# Huu_Binh_IOT.net
KiCad netlist of a schematic drawn in Altium Designer
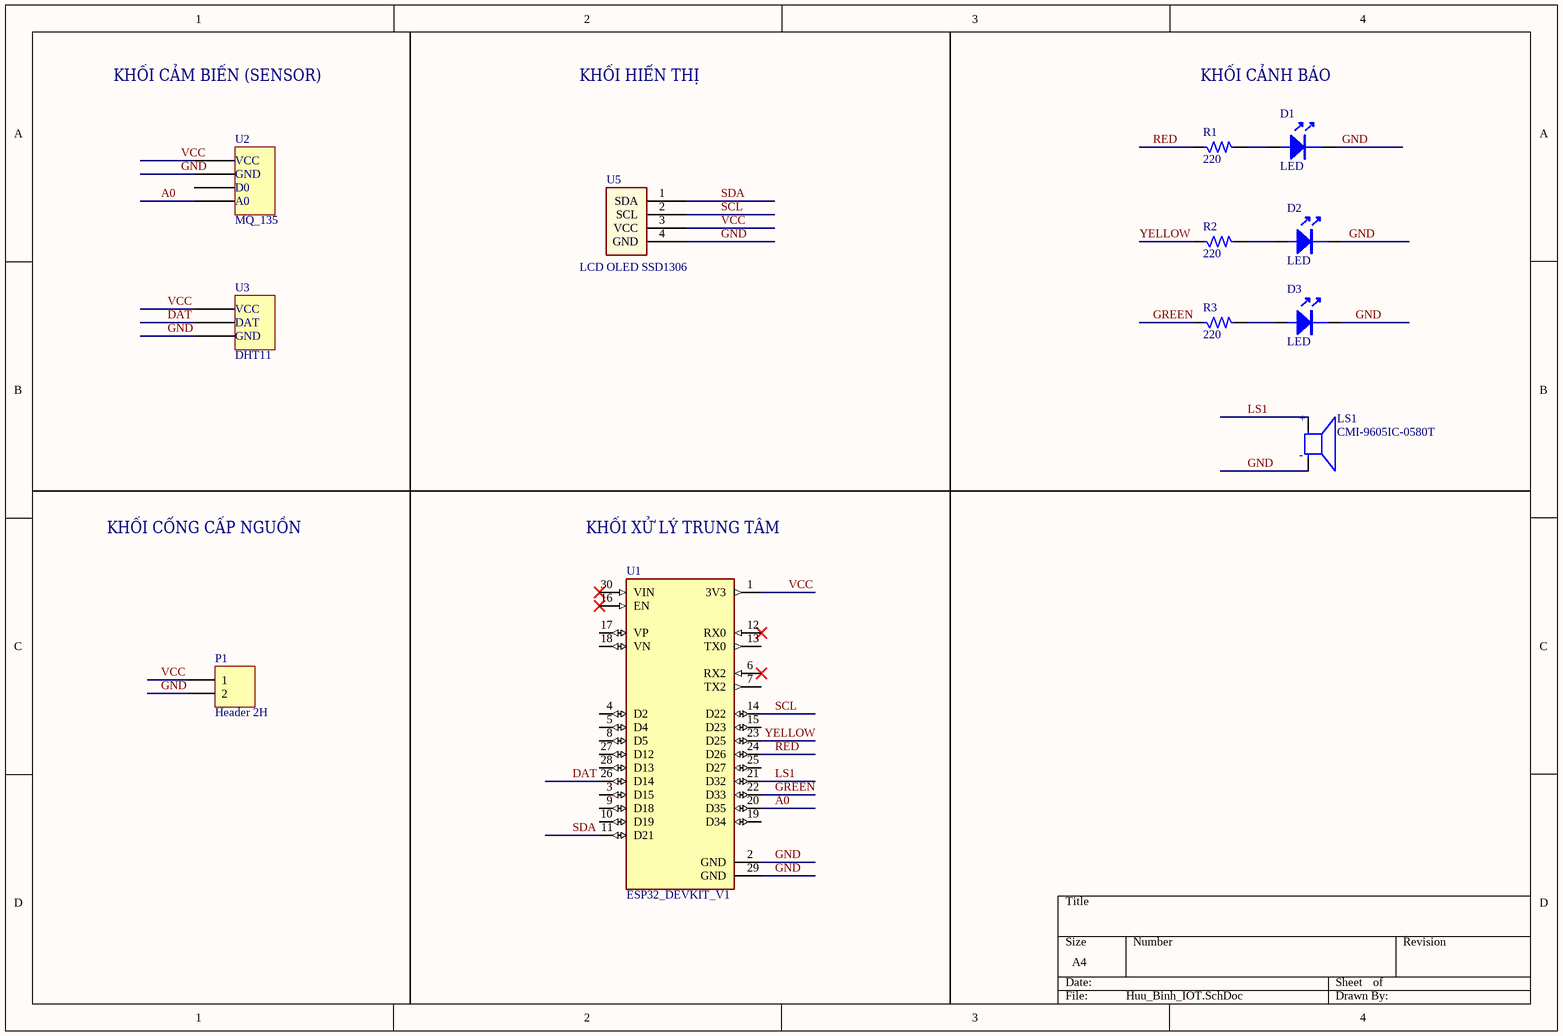
[diagram p0: Huu_Binh_IOT.SchDoc]

(export (version "E")
  (design (tool "Eeschema 10.0.6"))
  (components
    (comp (ref "D1") (value "LED") (footprint "CAP10UF") (libsource (lib "Devzone_SCHLib") (part "LED")))
    (comp (ref "D2") (value "LED") (footprint "CAP10UF") (libsource (lib "Devzone_SCHLib") (part "LED")))
    (comp (ref "D3") (value "LED") (footprint "CAP10UF") (libsource (lib "Devzone_SCHLib") (part "LED")))
    (comp (ref "LS1")
      (value "CMI-9605IC-0580T")
      (footprint "CUI_CMI-9605IC-0580T")
      (description "9.6 mm, 5 Vdc, 80 dB, Through Hole, Driving Circuit, Magnetic Audio Indicator Buzzer")
      (fields (field (name "MF") "Same Sky"))
      (libsource (lib "CMI-9605IC-0580T") (part "CMI-9605IC-0580T"))
    )
    (comp (ref "P1")
      (value "Header 2H")
      (footprint "HDR1X2H")
      (description "Header, 2-Pin, Right Angle")
      (fields (field (name "PUBLISHER") "Altium Limited"))
      (libsource (lib "Cty1") (part "Header 2H"))
    )
    (comp (ref "R1")
      (value "220")
      (footprint "R1/6W")
      (description "Resistor 1/4W")
      (libsource (lib "Devzone_SCHLib") (part "Res"))
    )
    (comp (ref "R2")
      (value "220")
      (footprint "R1/6W")
      (description "Resistor 1/4W")
      (libsource (lib "Devzone_SCHLib") (part "Res"))
    )
    (comp (ref "R3")
      (value "220")
      (footprint "R1/6W")
      (description "Resistor 1/4W")
      (libsource (lib "Devzone_SCHLib") (part "Res"))
    )
    (comp (ref "U1")
      (value "ESP32_DEVKIT_V1")
      (footprint "ESP32_DEVKIT_V1")
      (libsource (lib "ESP32_DEVKIT_V1") (part "ESP32_DEVKIT_V1"))
    )
    (comp (ref "U2") (value "MQ_135") (footprint "MQ_135") (libsource (lib "MQ_135_SCH") (part "MQ_135")))
    (comp (ref "U3") (value "DHT11") (footprint "DHT11") (libsource (lib "DHT11_SCH") (part "DHT11")))
    (comp (ref "U5")
      (value "LCD OLED SSD1306")
      (footprint "LCD SH1106")
      (libsource (lib "HoangLong_Library") (part "LCD SH1106"))
    )
  )
  (nets
    (net (code "1") (name "/A0") (class "Default")
      (node (ref "U1") (pin "20") (pinfunction "D35_20") (pintype "bidirectional"))
      (node (ref "U2") (pin "4") (pinfunction "3_4") (pintype "passive"))
    )
    (net (code "2") (name "/DAT") (class "Default")
      (node (ref "U1") (pin "26") (pinfunction "D14_26") (pintype "bidirectional"))
      (node (ref "U3") (pin "2") (pinfunction "2_2") (pintype "passive"))
    )
    (net (code "3") (name "/GND") (class "Default")
      (node (ref "D1") (pin "2") (pinfunction "2_2") (pintype "passive"))
      (node (ref "D2") (pin "2") (pinfunction "2_2") (pintype "passive"))
      (node (ref "D3") (pin "2") (pinfunction "2_2") (pintype "passive"))
      (node (ref "LS1") (pin "N") (pinfunction "N_N") (pintype "passive"))
      (node (ref "P1") (pin "2") (pinfunction "2_2") (pintype "passive"))
      (node (ref "U1") (pin "2") (pinfunction "GND_2") (pintype "power_in"))
      (node (ref "U1") (pin "29") (pinfunction "GND_29") (pintype "power_in"))
      (node (ref "U2") (pin "2") (pinfunction "2_2") (pintype "passive"))
      (node (ref "U3") (pin "3") (pinfunction "3_3") (pintype "passive"))
      (node (ref "U5") (pin "4") (pinfunction "GND_4") (pintype "passive"))
    )
    (net (code "4") (name "/GREEN") (class "Default")
      (node (ref "R3") (pin "1") (pinfunction "1_1") (pintype "passive"))
      (node (ref "U1") (pin "22") (pinfunction "D33_22") (pintype "bidirectional"))
    )
    (net (code "5") (name "/LS1") (class "Default")
      (node (ref "LS1") (pin "P") (pinfunction "P_P") (pintype "passive"))
      (node (ref "U1") (pin "21") (pinfunction "D32_21") (pintype "bidirectional"))
    )
    (net (code "6") (name "/RED") (class "Default")
      (node (ref "R1") (pin "1") (pinfunction "1_1") (pintype "passive"))
      (node (ref "U1") (pin "24") (pinfunction "D26_24") (pintype "bidirectional"))
    )
    (net (code "7") (name "/SCL") (class "Default")
      (node (ref "U1") (pin "14") (pinfunction "D22_14") (pintype "bidirectional"))
      (node (ref "U5") (pin "2") (pinfunction "SCL_2") (pintype "passive"))
    )
    (net (code "8") (name "/SDA") (class "Default")
      (node (ref "U1") (pin "11") (pinfunction "D21_11") (pintype "bidirectional"))
      (node (ref "U5") (pin "1") (pinfunction "SDA_1") (pintype "passive"))
    )
    (net (code "9") (name "/VCC") (class "Default")
      (node (ref "P1") (pin "1") (pinfunction "1_1") (pintype "passive"))
      (node (ref "U1") (pin "1") (pinfunction "3V3_1") (pintype "output"))
      (node (ref "U2") (pin "1") (pinfunction "1_1") (pintype "passive"))
      (node (ref "U3") (pin "1") (pinfunction "1_1") (pintype "passive"))
      (node (ref "U5") (pin "3") (pinfunction "VCC_3") (pintype "passive"))
    )
    (net (code "10") (name "/YELLOW") (class "Default")
      (node (ref "R2") (pin "1") (pinfunction "1_1") (pintype "passive"))
      (node (ref "U1") (pin "23") (pinfunction "D25_23") (pintype "bidirectional"))
    )
    (net (code "11") (name "Net-(D1-Pad1)") (class "Default")
      (node (ref "D1") (pin "1") (pinfunction "1_1") (pintype "passive"))
      (node (ref "R1") (pin "2") (pinfunction "2_2") (pintype "passive"))
    )
    (net (code "12") (name "Net-(D2-Pad1)") (class "Default")
      (node (ref "D2") (pin "1") (pinfunction "1_1") (pintype "passive"))
      (node (ref "R2") (pin "2") (pinfunction "2_2") (pintype "passive"))
    )
    (net (code "13") (name "Net-(D3-Pad1)") (class "Default")
      (node (ref "D3") (pin "1") (pinfunction "1_1") (pintype "passive"))
      (node (ref "R3") (pin "2") (pinfunction "2_2") (pintype "passive"))
    )
    (net (code "14") (name "unconnected-(U1-D2-Pad4)") (class "Default")
      (node (ref "U1") (pin "4") (pinfunction "D2_4") (pintype "bidirectional"))
    )
    (net (code "15") (name "unconnected-(U1-D4-Pad5)") (class "Default")
      (node (ref "U1") (pin "5") (pinfunction "D4_5") (pintype "bidirectional"))
    )
    (net (code "16") (name "unconnected-(U1-D5-Pad8)") (class "Default")
      (node (ref "U1") (pin "8") (pinfunction "D5_8") (pintype "bidirectional"))
    )
    (net (code "17") (name "unconnected-(U1-D12-Pad27)") (class "Default")
      (node (ref "U1") (pin "27") (pinfunction "D12_27") (pintype "bidirectional"))
    )
    (net (code "18") (name "unconnected-(U1-D13-Pad28)") (class "Default")
      (node (ref "U1") (pin "28") (pinfunction "D13_28") (pintype "bidirectional"))
    )
    (net (code "19") (name "unconnected-(U1-D15-Pad3)") (class "Default")
      (node (ref "U1") (pin "3") (pinfunction "D15_3") (pintype "bidirectional"))
    )
    (net (code "20") (name "unconnected-(U1-D18-Pad9)") (class "Default")
      (node (ref "U1") (pin "9") (pinfunction "D18_9") (pintype "bidirectional"))
    )
    (net (code "21") (name "unconnected-(U1-D19-Pad10)") (class "Default")
      (node (ref "U1") (pin "10") (pinfunction "D19_10") (pintype "bidirectional"))
    )
    (net (code "22") (name "unconnected-(U1-D23-Pad15)") (class "Default")
      (node (ref "U1") (pin "15") (pinfunction "D23_15") (pintype "bidirectional"))
    )
    (net (code "23") (name "unconnected-(U1-D27-Pad25)") (class "Default")
      (node (ref "U1") (pin "25") (pinfunction "D27_25") (pintype "bidirectional"))
    )
    (net (code "24") (name "unconnected-(U1-D34-Pad19)") (class "Default")
      (node (ref "U1") (pin "19") (pinfunction "D34_19") (pintype "bidirectional"))
    )
    (net (code "25") (name "unconnected-(U1-EN-Pad16)") (class "Default")
      (node (ref "U1") (pin "16") (pinfunction "EN_16") (pintype "input+no_connect"))
    )
    (net (code "26") (name "unconnected-(U1-RX0-Pad12)") (class "Default")
      (node (ref "U1") (pin "12") (pinfunction "RX0_12") (pintype "input+no_connect"))
    )
    (net (code "27") (name "unconnected-(U1-RX2-Pad6)") (class "Default")
      (node (ref "U1") (pin "6") (pinfunction "RX2_6") (pintype "input+no_connect"))
    )
    (net (code "28") (name "unconnected-(U1-TX0-Pad13)") (class "Default")
      (node (ref "U1") (pin "13") (pinfunction "TX0_13") (pintype "output"))
    )
    (net (code "29") (name "unconnected-(U1-TX2-Pad7)") (class "Default")
      (node (ref "U1") (pin "7") (pinfunction "TX2_7") (pintype "output"))
    )
    (net (code "30") (name "unconnected-(U1-VIN-Pad30)") (class "Default")
      (node (ref "U1") (pin "30") (pinfunction "VIN_30") (pintype "input+no_connect"))
    )
    (net (code "31") (name "unconnected-(U1-VN-Pad18)") (class "Default")
      (node (ref "U1") (pin "18") (pinfunction "VN_18") (pintype "bidirectional"))
    )
    (net (code "32") (name "unconnected-(U1-VP-Pad17)") (class "Default")
      (node (ref "U1") (pin "17") (pinfunction "VP_17") (pintype "bidirectional"))
    )
    (net (code "33") (name "unconnected-(U2-Pad3)") (class "Default")
      (node (ref "U2") (pin "3") (pinfunction "3_3") (pintype "passive"))
    )
  )
)
